# 3DEC8.net
KiCad netlist of a schematic drawn in EAGLE
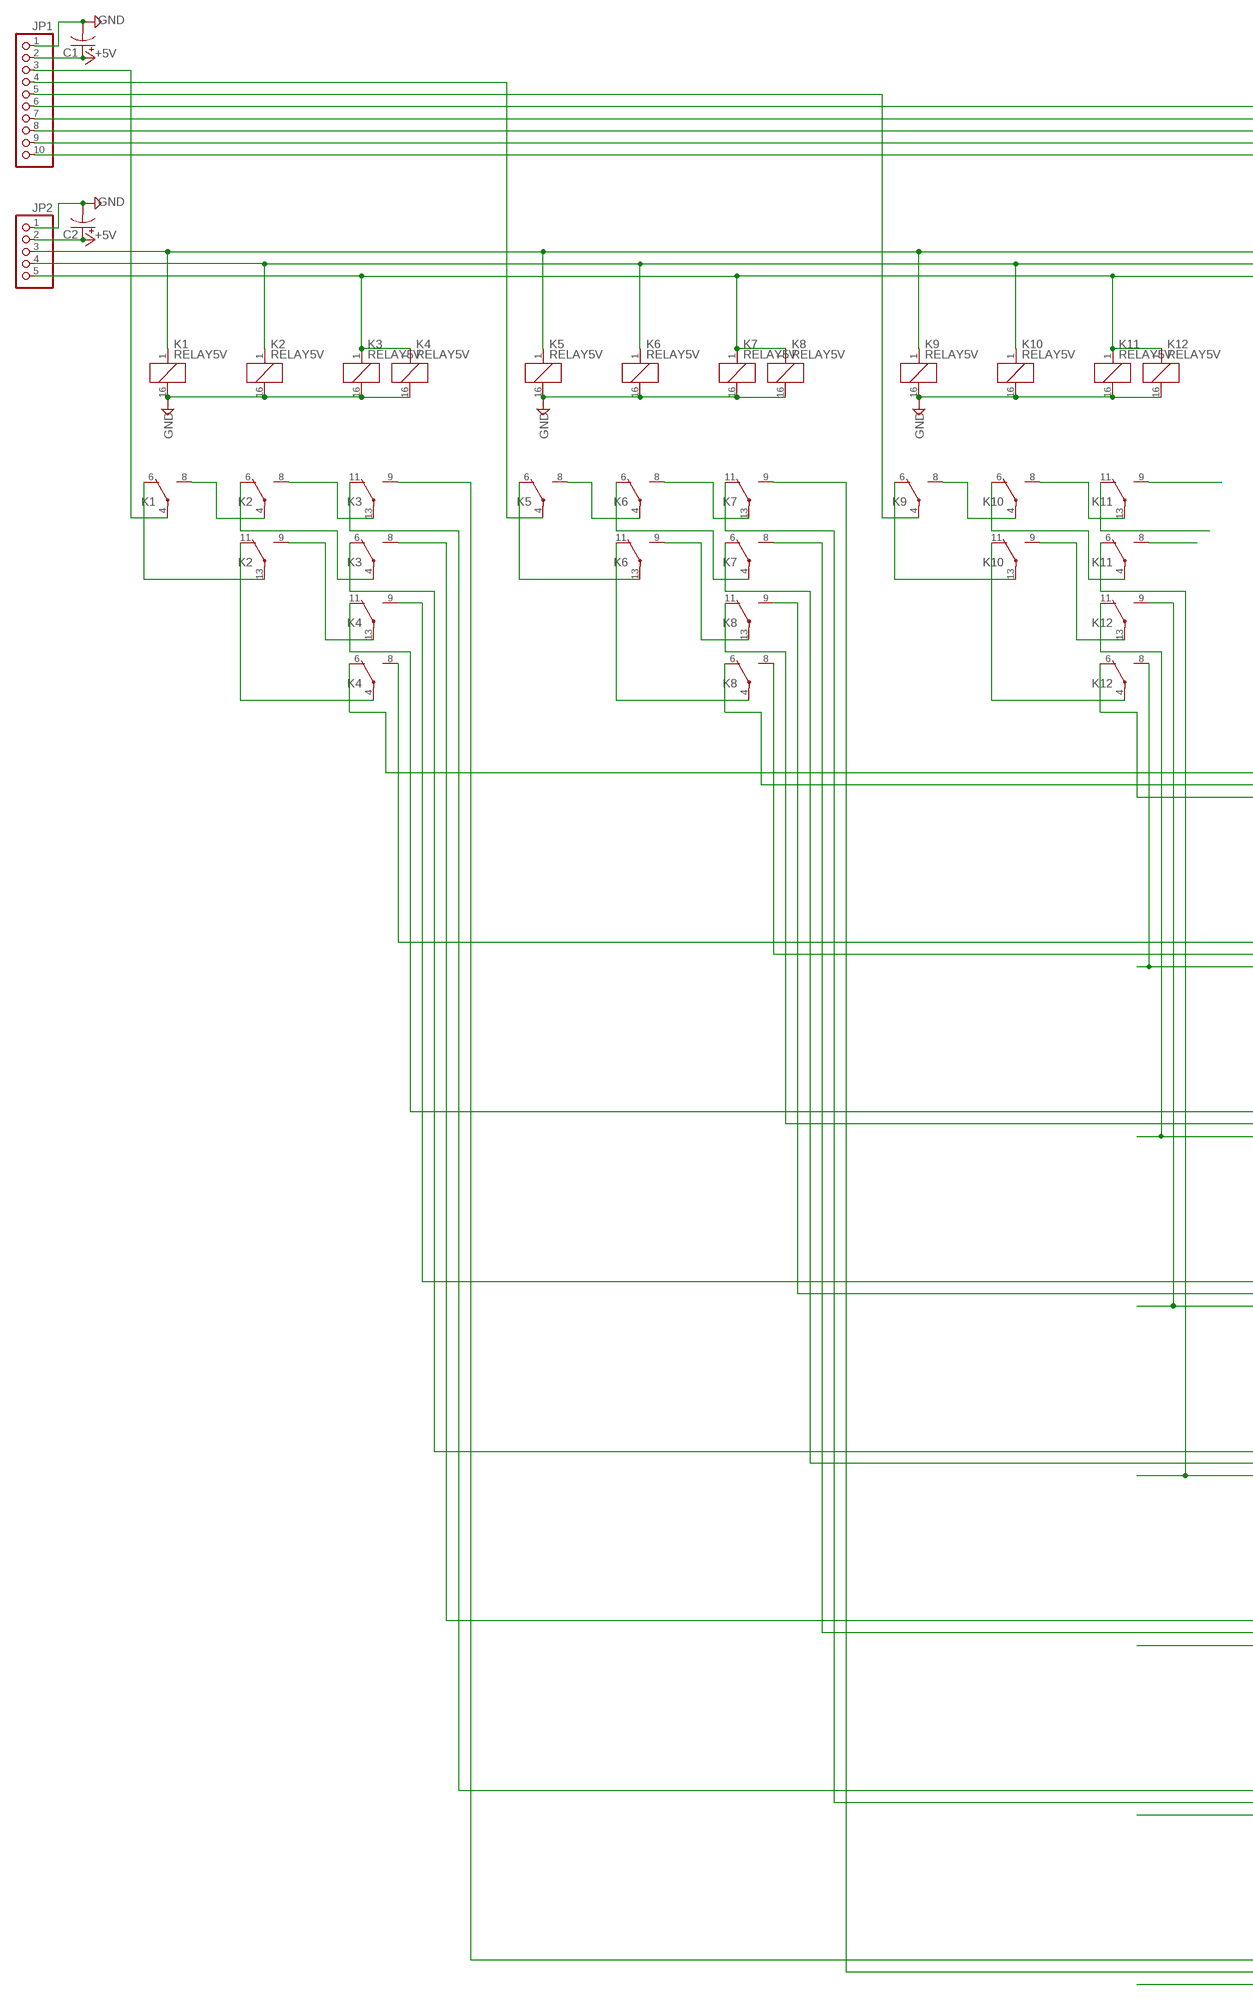
[diagram p0: schematic, sheet 1, part 1 of 2]
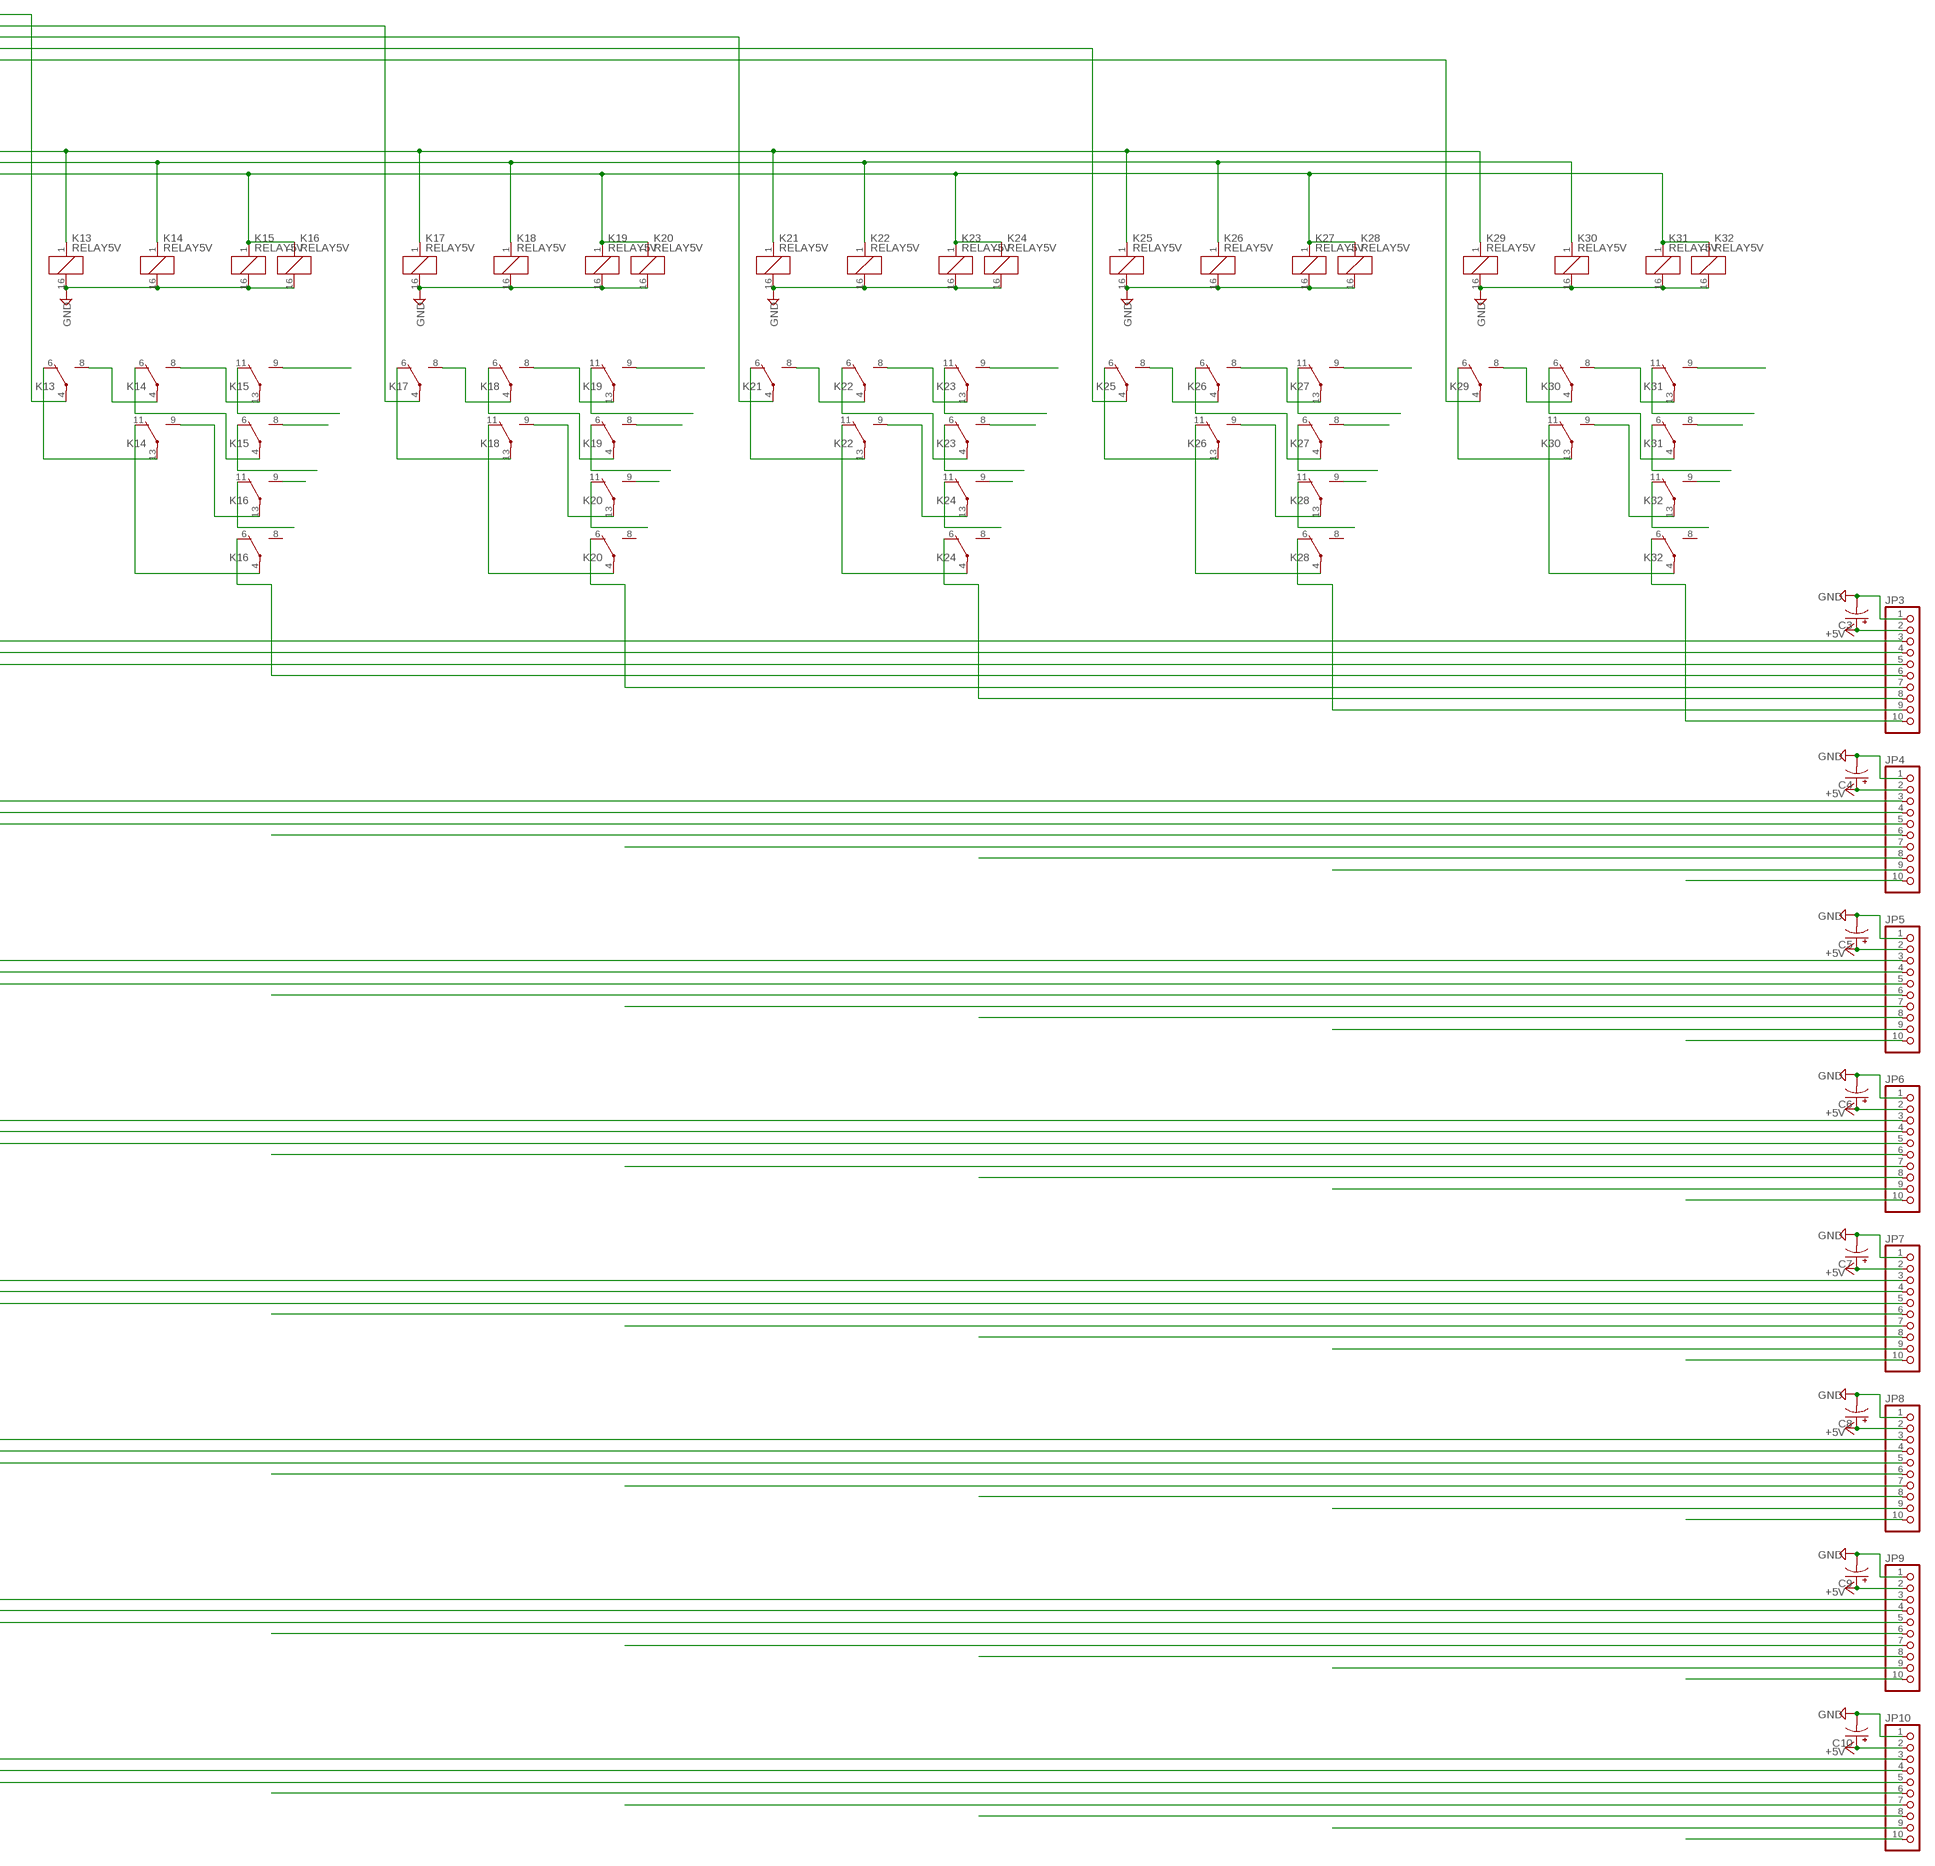
[diagram p1: schematic, sheet 1, part 2 of 2]

(export (version "E")
  (design (tool "Eeschema 10.0.6"))
  (components
    (comp (ref "C1")
      (value "CC-5-8.5")
      (footprint "eagle-import:E5-8,5")
      (libsource (lib "eagle-import") (part "CC-5-8.5"))
    )
    (comp (ref "C2")
      (value "CC-5-8.5")
      (footprint "eagle-import:E5-8,5")
      (libsource (lib "eagle-import") (part "CC-5-8.5"))
    )
    (comp (ref "C3")
      (value "CC-5-8.5")
      (footprint "eagle-import:E5-8,5")
      (libsource (lib "eagle-import") (part "CC-5-8.5"))
    )
    (comp (ref "C4")
      (value "CC-5-8.5")
      (footprint "eagle-import:E5-8,5")
      (libsource (lib "eagle-import") (part "CC-5-8.5"))
    )
    (comp (ref "C5")
      (value "CC-5-8.5")
      (footprint "eagle-import:E5-8,5")
      (libsource (lib "eagle-import") (part "CC-5-8.5"))
    )
    (comp (ref "C6")
      (value "CC-5-8.5")
      (footprint "eagle-import:E5-8,5")
      (libsource (lib "eagle-import") (part "CC-5-8.5"))
    )
    (comp (ref "C7")
      (value "CC-5-8.5")
      (footprint "eagle-import:E5-8,5")
      (libsource (lib "eagle-import") (part "CC-5-8.5"))
    )
    (comp (ref "C8")
      (value "CC-5-8.5")
      (footprint "eagle-import:E5-8,5")
      (libsource (lib "eagle-import") (part "CC-5-8.5"))
    )
    (comp (ref "C9")
      (value "CC-5-8.5")
      (footprint "eagle-import:E5-8,5")
      (libsource (lib "eagle-import") (part "CC-5-8.5"))
    )
    (comp (ref "C10")
      (value "CC-5-8.5")
      (footprint "eagle-import:E5-8,5")
      (libsource (lib "eagle-import") (part "CC-5-8.5"))
    )
    (comp (ref "JP1")
      (value "PINHD-1X10")
      (footprint "eagle-import:1X10")
      (libsource (lib "eagle-import") (part "PINHD-1X10"))
    )
    (comp (ref "JP2")
      (value "PINHD-1X5")
      (footprint "eagle-import:1X05")
      (libsource (lib "eagle-import") (part "PINHD-1X5"))
    )
    (comp (ref "JP3")
      (value "PINHD-1X10")
      (footprint "eagle-import:1X10")
      (libsource (lib "eagle-import") (part "PINHD-1X10"))
    )
    (comp (ref "JP4")
      (value "PINHD-1X10")
      (footprint "eagle-import:1X10")
      (libsource (lib "eagle-import") (part "PINHD-1X10"))
    )
    (comp (ref "JP5")
      (value "PINHD-1X10")
      (footprint "eagle-import:1X10")
      (libsource (lib "eagle-import") (part "PINHD-1X10"))
    )
    (comp (ref "JP6")
      (value "PINHD-1X10")
      (footprint "eagle-import:1X10")
      (libsource (lib "eagle-import") (part "PINHD-1X10"))
    )
    (comp (ref "JP7")
      (value "PINHD-1X10")
      (footprint "eagle-import:1X10")
      (libsource (lib "eagle-import") (part "PINHD-1X10"))
    )
    (comp (ref "JP8")
      (value "PINHD-1X10")
      (footprint "eagle-import:1X10")
      (libsource (lib "eagle-import") (part "PINHD-1X10"))
    )
    (comp (ref "JP9")
      (value "PINHD-1X10")
      (footprint "eagle-import:1X10")
      (libsource (lib "eagle-import") (part "PINHD-1X10"))
    )
    (comp (ref "JP10")
      (value "PINHD-1X10")
      (footprint "eagle-import:1X10")
      (libsource (lib "eagle-import") (part "PINHD-1X10"))
    )
    (comp (ref "K1")
      (value "RELAY5V")
      (footprint "eagle-import:DS-BT")
      (libsource (lib "eagle-import") (part "RELAY5V"))
    )
    (comp (ref "K2")
      (value "RELAY5V")
      (footprint "eagle-import:DS-BT")
      (libsource (lib "eagle-import") (part "RELAY5V"))
    )
    (comp (ref "K3")
      (value "RELAY5V")
      (footprint "eagle-import:DS-BT")
      (libsource (lib "eagle-import") (part "RELAY5V"))
    )
    (comp (ref "K4")
      (value "RELAY5V")
      (footprint "eagle-import:DS-BT")
      (libsource (lib "eagle-import") (part "RELAY5V"))
    )
    (comp (ref "K5")
      (value "RELAY5V")
      (footprint "eagle-import:DS-BT")
      (libsource (lib "eagle-import") (part "RELAY5V"))
    )
    (comp (ref "K6")
      (value "RELAY5V")
      (footprint "eagle-import:DS-BT")
      (libsource (lib "eagle-import") (part "RELAY5V"))
    )
    (comp (ref "K7")
      (value "RELAY5V")
      (footprint "eagle-import:DS-BT")
      (libsource (lib "eagle-import") (part "RELAY5V"))
    )
    (comp (ref "K8")
      (value "RELAY5V")
      (footprint "eagle-import:DS-BT")
      (libsource (lib "eagle-import") (part "RELAY5V"))
    )
    (comp (ref "K9")
      (value "RELAY5V")
      (footprint "eagle-import:DS-BT")
      (libsource (lib "eagle-import") (part "RELAY5V"))
    )
    (comp (ref "K10")
      (value "RELAY5V")
      (footprint "eagle-import:DS-BT")
      (libsource (lib "eagle-import") (part "RELAY5V"))
    )
    (comp (ref "K11")
      (value "RELAY5V")
      (footprint "eagle-import:DS-BT")
      (libsource (lib "eagle-import") (part "RELAY5V"))
    )
    (comp (ref "K12")
      (value "RELAY5V")
      (footprint "eagle-import:DS-BT")
      (libsource (lib "eagle-import") (part "RELAY5V"))
    )
    (comp (ref "K13")
      (value "RELAY5V")
      (footprint "eagle-import:DS-BT")
      (libsource (lib "eagle-import") (part "RELAY5V"))
    )
    (comp (ref "K14")
      (value "RELAY5V")
      (footprint "eagle-import:DS-BT")
      (libsource (lib "eagle-import") (part "RELAY5V"))
    )
    (comp (ref "K15")
      (value "RELAY5V")
      (footprint "eagle-import:DS-BT")
      (libsource (lib "eagle-import") (part "RELAY5V"))
    )
    (comp (ref "K16")
      (value "RELAY5V")
      (footprint "eagle-import:DS-BT")
      (libsource (lib "eagle-import") (part "RELAY5V"))
    )
    (comp (ref "K17")
      (value "RELAY5V")
      (footprint "eagle-import:DS-BT")
      (libsource (lib "eagle-import") (part "RELAY5V"))
    )
    (comp (ref "K18")
      (value "RELAY5V")
      (footprint "eagle-import:DS-BT")
      (libsource (lib "eagle-import") (part "RELAY5V"))
    )
    (comp (ref "K19")
      (value "RELAY5V")
      (footprint "eagle-import:DS-BT")
      (libsource (lib "eagle-import") (part "RELAY5V"))
    )
    (comp (ref "K20")
      (value "RELAY5V")
      (footprint "eagle-import:DS-BT")
      (libsource (lib "eagle-import") (part "RELAY5V"))
    )
    (comp (ref "K21")
      (value "RELAY5V")
      (footprint "eagle-import:DS-BT")
      (libsource (lib "eagle-import") (part "RELAY5V"))
    )
    (comp (ref "K22")
      (value "RELAY5V")
      (footprint "eagle-import:DS-BT")
      (libsource (lib "eagle-import") (part "RELAY5V"))
    )
    (comp (ref "K23")
      (value "RELAY5V")
      (footprint "eagle-import:DS-BT")
      (libsource (lib "eagle-import") (part "RELAY5V"))
    )
    (comp (ref "K24")
      (value "RELAY5V")
      (footprint "eagle-import:DS-BT")
      (libsource (lib "eagle-import") (part "RELAY5V"))
    )
    (comp (ref "K25")
      (value "RELAY5V")
      (footprint "eagle-import:DS-BT")
      (libsource (lib "eagle-import") (part "RELAY5V"))
    )
    (comp (ref "K26")
      (value "RELAY5V")
      (footprint "eagle-import:DS-BT")
      (libsource (lib "eagle-import") (part "RELAY5V"))
    )
    (comp (ref "K27")
      (value "RELAY5V")
      (footprint "eagle-import:DS-BT")
      (libsource (lib "eagle-import") (part "RELAY5V"))
    )
    (comp (ref "K28")
      (value "RELAY5V")
      (footprint "eagle-import:DS-BT")
      (libsource (lib "eagle-import") (part "RELAY5V"))
    )
    (comp (ref "K29")
      (value "RELAY5V")
      (footprint "eagle-import:DS-BT")
      (libsource (lib "eagle-import") (part "RELAY5V"))
    )
    (comp (ref "K30")
      (value "RELAY5V")
      (footprint "eagle-import:DS-BT")
      (libsource (lib "eagle-import") (part "RELAY5V"))
    )
    (comp (ref "K31")
      (value "RELAY5V")
      (footprint "eagle-import:DS-BT")
      (libsource (lib "eagle-import") (part "RELAY5V"))
    )
    (comp (ref "K32")
      (value "RELAY5V")
      (footprint "eagle-import:DS-BT")
      (libsource (lib "eagle-import") (part "RELAY5V"))
    )
  )
  (nets
    (net (code "1") (name "+5V") (class "Default")
      (node (ref "C1") (pin "+") (pinfunction "+_+") (pintype "passive"))
      (node (ref "C10") (pin "+") (pinfunction "+_+") (pintype "passive"))
      (node (ref "C2") (pin "+") (pinfunction "+_+") (pintype "passive"))
      (node (ref "C3") (pin "+") (pinfunction "+_+") (pintype "passive"))
      (node (ref "C4") (pin "+") (pinfunction "+_+") (pintype "passive"))
      (node (ref "C5") (pin "+") (pinfunction "+_+") (pintype "passive"))
      (node (ref "C6") (pin "+") (pinfunction "+_+") (pintype "passive"))
      (node (ref "C7") (pin "+") (pinfunction "+_+") (pintype "passive"))
      (node (ref "C8") (pin "+") (pinfunction "+_+") (pintype "passive"))
      (node (ref "C9") (pin "+") (pinfunction "+_+") (pintype "passive"))
      (node (ref "JP1") (pin "2") (pinfunction "2_2") (pintype "passive"))
      (node (ref "JP10") (pin "2") (pinfunction "2_2") (pintype "passive"))
      (node (ref "JP2") (pin "2") (pinfunction "2_2") (pintype "passive"))
      (node (ref "JP3") (pin "2") (pinfunction "2_2") (pintype "passive"))
      (node (ref "JP4") (pin "2") (pinfunction "2_2") (pintype "passive"))
      (node (ref "JP5") (pin "2") (pinfunction "2_2") (pintype "passive"))
      (node (ref "JP6") (pin "2") (pinfunction "2_2") (pintype "passive"))
      (node (ref "JP7") (pin "2") (pinfunction "2_2") (pintype "passive"))
      (node (ref "JP8") (pin "2") (pinfunction "2_2") (pintype "passive"))
      (node (ref "JP9") (pin "2") (pinfunction "2_2") (pintype "passive"))
    )
    (net (code "2") (name "GND") (class "Default")
      (node (ref "C1") (pin "-") (pinfunction "-_-") (pintype "passive"))
      (node (ref "C10") (pin "-") (pinfunction "-_-") (pintype "passive"))
      (node (ref "C2") (pin "-") (pinfunction "-_-") (pintype "passive"))
      (node (ref "C3") (pin "-") (pinfunction "-_-") (pintype "passive"))
      (node (ref "C4") (pin "-") (pinfunction "-_-") (pintype "passive"))
      (node (ref "C5") (pin "-") (pinfunction "-_-") (pintype "passive"))
      (node (ref "C6") (pin "-") (pinfunction "-_-") (pintype "passive"))
      (node (ref "C7") (pin "-") (pinfunction "-_-") (pintype "passive"))
      (node (ref "C8") (pin "-") (pinfunction "-_-") (pintype "passive"))
      (node (ref "C9") (pin "-") (pinfunction "-_-") (pintype "passive"))
      (node (ref "JP1") (pin "1") (pinfunction "1_1") (pintype "passive"))
      (node (ref "JP10") (pin "1") (pinfunction "1_1") (pintype "passive"))
      (node (ref "JP2") (pin "1") (pinfunction "1_1") (pintype "passive"))
      (node (ref "JP3") (pin "1") (pinfunction "1_1") (pintype "passive"))
      (node (ref "JP4") (pin "1") (pinfunction "1_1") (pintype "passive"))
      (node (ref "JP5") (pin "1") (pinfunction "1_1") (pintype "passive"))
      (node (ref "JP6") (pin "1") (pinfunction "1_1") (pintype "passive"))
      (node (ref "JP7") (pin "1") (pinfunction "1_1") (pintype "passive"))
      (node (ref "JP8") (pin "1") (pinfunction "1_1") (pintype "passive"))
      (node (ref "JP9") (pin "1") (pinfunction "1_1") (pintype "passive"))
      (node (ref "K1") (pin "16") (pinfunction "-_16") (pintype "passive"))
      (node (ref "K10") (pin "16") (pinfunction "-_16") (pintype "passive"))
      (node (ref "K11") (pin "16") (pinfunction "-_16") (pintype "passive"))
      (node (ref "K12") (pin "16") (pinfunction "-_16") (pintype "passive"))
      (node (ref "K13") (pin "16") (pinfunction "-_16") (pintype "passive"))
      (node (ref "K14") (pin "16") (pinfunction "-_16") (pintype "passive"))
      (node (ref "K15") (pin "16") (pinfunction "-_16") (pintype "passive"))
      (node (ref "K16") (pin "16") (pinfunction "-_16") (pintype "passive"))
      (node (ref "K17") (pin "16") (pinfunction "-_16") (pintype "passive"))
      (node (ref "K18") (pin "16") (pinfunction "-_16") (pintype "passive"))
      (node (ref "K19") (pin "16") (pinfunction "-_16") (pintype "passive"))
      (node (ref "K2") (pin "16") (pinfunction "-_16") (pintype "passive"))
      (node (ref "K20") (pin "16") (pinfunction "-_16") (pintype "passive"))
      (node (ref "K21") (pin "16") (pinfunction "-_16") (pintype "passive"))
      (node (ref "K22") (pin "16") (pinfunction "-_16") (pintype "passive"))
      (node (ref "K23") (pin "16") (pinfunction "-_16") (pintype "passive"))
      (node (ref "K24") (pin "16") (pinfunction "-_16") (pintype "passive"))
      (node (ref "K25") (pin "16") (pinfunction "-_16") (pintype "passive"))
      (node (ref "K26") (pin "16") (pinfunction "-_16") (pintype "passive"))
      (node (ref "K27") (pin "16") (pinfunction "-_16") (pintype "passive"))
      (node (ref "K28") (pin "16") (pinfunction "-_16") (pintype "passive"))
      (node (ref "K29") (pin "16") (pinfunction "-_16") (pintype "passive"))
      (node (ref "K3") (pin "16") (pinfunction "-_16") (pintype "passive"))
      (node (ref "K30") (pin "16") (pinfunction "-_16") (pintype "passive"))
      (node (ref "K31") (pin "16") (pinfunction "-_16") (pintype "passive"))
      (node (ref "K32") (pin "16") (pinfunction "-_16") (pintype "passive"))
      (node (ref "K4") (pin "16") (pinfunction "-_16") (pintype "passive"))
      (node (ref "K5") (pin "16") (pinfunction "-_16") (pintype "passive"))
      (node (ref "K6") (pin "16") (pinfunction "-_16") (pintype "passive"))
      (node (ref "K7") (pin "16") (pinfunction "-_16") (pintype "passive"))
      (node (ref "K8") (pin "16") (pinfunction "-_16") (pintype "passive"))
      (node (ref "K9") (pin "16") (pinfunction "-_16") (pintype "passive"))
    )
    (net (code "3") (name "Net-(K1B-O)") (class "Default")
      (node (ref "K1") (pin "6") (pinfunction "O_6") (pintype "passive"))
      (node (ref "K2") (pin "13") (pinfunction "P_13") (pintype "passive"))
    )
    (net (code "4") (name "Net-(K1B-P)") (class "Default")
      (node (ref "JP1") (pin "3") (pinfunction "3_3") (pintype "passive"))
      (node (ref "K1") (pin "4") (pinfunction "P_4") (pintype "passive"))
    )
    (net (code "5") (name "Net-(K1B-S)") (class "Default")
      (node (ref "K1") (pin "8") (pinfunction "S_8") (pintype "passive"))
      (node (ref "K2") (pin "4") (pinfunction "P_4") (pintype "passive"))
    )
    (net (code "6") (name "Net-(K2B-O)") (class "Default")
      (node (ref "K2") (pin "6") (pinfunction "O_6") (pintype "passive"))
      (node (ref "K3") (pin "4") (pinfunction "P_4") (pintype "passive"))
    )
    (net (code "7") (name "Net-(K2B-S)") (class "Default")
      (node (ref "K2") (pin "8") (pinfunction "S_8") (pintype "passive"))
      (node (ref "K3") (pin "13") (pinfunction "P_13") (pintype "passive"))
    )
    (net (code "8") (name "Net-(K2C-O)") (class "Default")
      (node (ref "K2") (pin "11") (pinfunction "O_11") (pintype "passive"))
      (node (ref "K4") (pin "4") (pinfunction "P_4") (pintype "passive"))
    )
    (net (code "9") (name "Net-(K2C-S)") (class "Default")
      (node (ref "K2") (pin "9") (pinfunction "S_9") (pintype "passive"))
      (node (ref "K4") (pin "13") (pinfunction "P_13") (pintype "passive"))
    )
    (net (code "10") (name "Net-(K3B-O)") (class "Default")
      (node (ref "JP7") (pin "3") (pinfunction "3_3") (pintype "passive"))
      (node (ref "K3") (pin "6") (pinfunction "O_6") (pintype "passive"))
    )
    (net (code "11") (name "Net-(K3B-S)") (class "Default")
      (node (ref "JP8") (pin "3") (pinfunction "3_3") (pintype "passive"))
      (node (ref "K3") (pin "8") (pinfunction "S_8") (pintype "passive"))
    )
    (net (code "12") (name "Net-(K3C-O)") (class "Default")
      (node (ref "JP9") (pin "3") (pinfunction "3_3") (pintype "passive"))
      (node (ref "K3") (pin "11") (pinfunction "O_11") (pintype "passive"))
    )
    (net (code "13") (name "Net-(K3C-S)") (class "Default")
      (node (ref "JP10") (pin "3") (pinfunction "3_3") (pintype "passive"))
      (node (ref "K3") (pin "9") (pinfunction "S_9") (pintype "passive"))
    )
    (net (code "14") (name "Net-(K4B-O)") (class "Default")
      (node (ref "JP3") (pin "3") (pinfunction "3_3") (pintype "passive"))
      (node (ref "K4") (pin "6") (pinfunction "O_6") (pintype "passive"))
    )
    (net (code "15") (name "Net-(K4B-S)") (class "Default")
      (node (ref "JP4") (pin "3") (pinfunction "3_3") (pintype "passive"))
      (node (ref "K4") (pin "8") (pinfunction "S_8") (pintype "passive"))
    )
    (net (code "16") (name "Net-(K4C-O)") (class "Default")
      (node (ref "JP5") (pin "3") (pinfunction "3_3") (pintype "passive"))
      (node (ref "K4") (pin "11") (pinfunction "O_11") (pintype "passive"))
    )
    (net (code "17") (name "Net-(K4C-S)") (class "Default")
      (node (ref "JP6") (pin "3") (pinfunction "3_3") (pintype "passive"))
      (node (ref "K4") (pin "9") (pinfunction "S_9") (pintype "passive"))
    )
    (net (code "18") (name "Net-(K5B-O)") (class "Default")
      (node (ref "K5") (pin "6") (pinfunction "O_6") (pintype "passive"))
      (node (ref "K6") (pin "13") (pinfunction "P_13") (pintype "passive"))
    )
    (net (code "19") (name "Net-(K5B-P)") (class "Default")
      (node (ref "JP1") (pin "4") (pinfunction "4_4") (pintype "passive"))
      (node (ref "K5") (pin "4") (pinfunction "P_4") (pintype "passive"))
    )
    (net (code "20") (name "Net-(K5B-S)") (class "Default")
      (node (ref "K5") (pin "8") (pinfunction "S_8") (pintype "passive"))
      (node (ref "K6") (pin "4") (pinfunction "P_4") (pintype "passive"))
    )
    (net (code "21") (name "Net-(K6B-O)") (class "Default")
      (node (ref "K6") (pin "6") (pinfunction "O_6") (pintype "passive"))
      (node (ref "K7") (pin "4") (pinfunction "P_4") (pintype "passive"))
    )
    (net (code "22") (name "Net-(K6B-S)") (class "Default")
      (node (ref "K6") (pin "8") (pinfunction "S_8") (pintype "passive"))
      (node (ref "K7") (pin "13") (pinfunction "P_13") (pintype "passive"))
    )
    (net (code "23") (name "Net-(K6C-O)") (class "Default")
      (node (ref "K6") (pin "11") (pinfunction "O_11") (pintype "passive"))
      (node (ref "K8") (pin "4") (pinfunction "P_4") (pintype "passive"))
    )
    (net (code "24") (name "Net-(K6C-S)") (class "Default")
      (node (ref "K6") (pin "9") (pinfunction "S_9") (pintype "passive"))
      (node (ref "K8") (pin "13") (pinfunction "P_13") (pintype "passive"))
    )
    (net (code "25") (name "Net-(K7B-O)") (class "Default")
      (node (ref "JP7") (pin "4") (pinfunction "4_4") (pintype "passive"))
      (node (ref "K7") (pin "6") (pinfunction "O_6") (pintype "passive"))
    )
    (net (code "26") (name "Net-(K7B-S)") (class "Default")
      (node (ref "JP8") (pin "4") (pinfunction "4_4") (pintype "passive"))
      (node (ref "K7") (pin "8") (pinfunction "S_8") (pintype "passive"))
    )
    (net (code "27") (name "Net-(K7C-O)") (class "Default")
      (node (ref "JP9") (pin "4") (pinfunction "4_4") (pintype "passive"))
      (node (ref "K7") (pin "11") (pinfunction "O_11") (pintype "passive"))
    )
    (net (code "28") (name "Net-(K7C-S)") (class "Default")
      (node (ref "JP10") (pin "4") (pinfunction "4_4") (pintype "passive"))
      (node (ref "K7") (pin "9") (pinfunction "S_9") (pintype "passive"))
    )
    (net (code "29") (name "Net-(K8B-O)") (class "Default")
      (node (ref "JP3") (pin "4") (pinfunction "4_4") (pintype "passive"))
      (node (ref "K8") (pin "6") (pinfunction "O_6") (pintype "passive"))
    )
    (net (code "30") (name "Net-(K8B-S)") (class "Default")
      (node (ref "JP4") (pin "4") (pinfunction "4_4") (pintype "passive"))
      (node (ref "K8") (pin "8") (pinfunction "S_8") (pintype "passive"))
    )
    (net (code "31") (name "Net-(K8C-O)") (class "Default")
      (node (ref "JP5") (pin "4") (pinfunction "4_4") (pintype "passive"))
      (node (ref "K8") (pin "11") (pinfunction "O_11") (pintype "passive"))
    )
    (net (code "32") (name "Net-(K8C-S)") (class "Default")
      (node (ref "JP6") (pin "4") (pinfunction "4_4") (pintype "passive"))
      (node (ref "K8") (pin "9") (pinfunction "S_9") (pintype "passive"))
    )
    (net (code "33") (name "Net-(K9B-P)") (class "Default")
      (node (ref "JP1") (pin "5") (pinfunction "5_5") (pintype "passive"))
      (node (ref "K9") (pin "4") (pinfunction "P_4") (pintype "passive"))
    )
    (net (code "34") (name "Net-(K10A-+)") (class "Default")
      (node (ref "JP2") (pin "4") (pinfunction "4_4") (pintype "passive"))
      (node (ref "K10") (pin "1") (pinfunction "+_1") (pintype "passive"))
      (node (ref "K14") (pin "1") (pinfunction "+_1") (pintype "passive"))
      (node (ref "K18") (pin "1") (pinfunction "+_1") (pintype "passive"))
      (node (ref "K2") (pin "1") (pinfunction "+_1") (pintype "passive"))
      (node (ref "K22") (pin "1") (pinfunction "+_1") (pintype "passive"))
      (node (ref "K26") (pin "1") (pinfunction "+_1") (pintype "passive"))
      (node (ref "K30") (pin "1") (pinfunction "+_1") (pintype "passive"))
      (node (ref "K6") (pin "1") (pinfunction "+_1") (pintype "passive"))
    )
    (net (code "35") (name "Net-(K10B-O)") (class "Default")
      (node (ref "K10") (pin "6") (pinfunction "O_6") (pintype "passive"))
      (node (ref "K11") (pin "4") (pinfunction "P_4") (pintype "passive"))
    )
    (net (code "36") (name "Net-(K10B-P)") (class "Default")
      (node (ref "K10") (pin "4") (pinfunction "P_4") (pintype "passive"))
      (node (ref "K9") (pin "8") (pinfunction "S_8") (pintype "passive"))
    )
    (net (code "37") (name "Net-(K10B-S)") (class "Default")
      (node (ref "K10") (pin "8") (pinfunction "S_8") (pintype "passive"))
      (node (ref "K11") (pin "13") (pinfunction "P_13") (pintype "passive"))
    )
    (net (code "38") (name "Net-(K10C-O)") (class "Default")
      (node (ref "K10") (pin "11") (pinfunction "O_11") (pintype "passive"))
      (node (ref "K12") (pin "4") (pinfunction "P_4") (pintype "passive"))
    )
    (net (code "39") (name "Net-(K10C-P)") (class "Default")
      (node (ref "K10") (pin "13") (pinfunction "P_13") (pintype "passive"))
      (node (ref "K9") (pin "6") (pinfunction "O_6") (pintype "passive"))
    )
    (net (code "40") (name "Net-(K10C-S)") (class "Default")
      (node (ref "K10") (pin "9") (pinfunction "S_9") (pintype "passive"))
      (node (ref "K12") (pin "13") (pinfunction "P_13") (pintype "passive"))
    )
    (net (code "41") (name "Net-(K11A-+)") (class "Default")
      (node (ref "JP2") (pin "5") (pinfunction "5_5") (pintype "passive"))
      (node (ref "K11") (pin "1") (pinfunction "+_1") (pintype "passive"))
      (node (ref "K12") (pin "1") (pinfunction "+_1") (pintype "passive"))
      (node (ref "K15") (pin "1") (pinfunction "+_1") (pintype "passive"))
      (node (ref "K16") (pin "1") (pinfunction "+_1") (pintype "passive"))
      (node (ref "K19") (pin "1") (pinfunction "+_1") (pintype "passive"))
      (node (ref "K20") (pin "1") (pinfunction "+_1") (pintype "passive"))
      (node (ref "K23") (pin "1") (pinfunction "+_1") (pintype "passive"))
      (node (ref "K24") (pin "1") (pinfunction "+_1") (pintype "passive"))
      (node (ref "K27") (pin "1") (pinfunction "+_1") (pintype "passive"))
      (node (ref "K28") (pin "1") (pinfunction "+_1") (pintype "passive"))
      (node (ref "K3") (pin "1") (pinfunction "+_1") (pintype "passive"))
      (node (ref "K31") (pin "1") (pinfunction "+_1") (pintype "passive"))
      (node (ref "K32") (pin "1") (pinfunction "+_1") (pintype "passive"))
      (node (ref "K4") (pin "1") (pinfunction "+_1") (pintype "passive"))
      (node (ref "K7") (pin "1") (pinfunction "+_1") (pintype "passive"))
      (node (ref "K8") (pin "1") (pinfunction "+_1") (pintype "passive"))
    )
    (net (code "42") (name "Net-(K11B-O)") (class "Default")
      (node (ref "JP7") (pin "5") (pinfunction "5_5") (pintype "passive"))
      (node (ref "K11") (pin "6") (pinfunction "O_6") (pintype "passive"))
    )
    (net (code "43") (name "Net-(K12B-O)") (class "Default")
      (node (ref "JP3") (pin "5") (pinfunction "5_5") (pintype "passive"))
      (node (ref "K12") (pin "6") (pinfunction "O_6") (pintype "passive"))
    )
    (net (code "44") (name "Net-(K12B-S)") (class "Default")
      (node (ref "JP4") (pin "5") (pinfunction "5_5") (pintype "passive"))
      (node (ref "K12") (pin "8") (pinfunction "S_8") (pintype "passive"))
    )
    (net (code "45") (name "Net-(K12C-O)") (class "Default")
      (node (ref "JP5") (pin "5") (pinfunction "5_5") (pintype "passive"))
      (node (ref "K12") (pin "11") (pinfunction "O_11") (pintype "passive"))
    )
    (net (code "46") (name "Net-(K12C-S)") (class "Default")
      (node (ref "JP6") (pin "5") (pinfunction "5_5") (pintype "passive"))
      (node (ref "K12") (pin "9") (pinfunction "S_9") (pintype "passive"))
    )
    (net (code "47") (name "Net-(K13A-+)") (class "Default")
      (node (ref "JP2") (pin "3") (pinfunction "3_3") (pintype "passive"))
      (node (ref "K1") (pin "1") (pinfunction "+_1") (pintype "passive"))
      (node (ref "K13") (pin "1") (pinfunction "+_1") (pintype "passive"))
      (node (ref "K17") (pin "1") (pinfunction "+_1") (pintype "passive"))
      (node (ref "K21") (pin "1") (pinfunction "+_1") (pintype "passive"))
      (node (ref "K25") (pin "1") (pinfunction "+_1") (pintype "passive"))
      (node (ref "K29") (pin "1") (pinfunction "+_1") (pintype "passive"))
      (node (ref "K5") (pin "1") (pinfunction "+_1") (pintype "passive"))
      (node (ref "K9") (pin "1") (pinfunction "+_1") (pintype "passive"))
    )
    (net (code "48") (name "Net-(K13B-O)") (class "Default")
      (node (ref "K13") (pin "6") (pinfunction "O_6") (pintype "passive"))
      (node (ref "K14") (pin "13") (pinfunction "P_13") (pintype "passive"))
    )
    (net (code "49") (name "Net-(K13B-P)") (class "Default")
      (node (ref "JP1") (pin "6") (pinfunction "6_6") (pintype "passive"))
      (node (ref "K13") (pin "4") (pinfunction "P_4") (pintype "passive"))
    )
    (net (code "50") (name "Net-(K13B-S)") (class "Default")
      (node (ref "K13") (pin "8") (pinfunction "S_8") (pintype "passive"))
      (node (ref "K14") (pin "4") (pinfunction "P_4") (pintype "passive"))
    )
    (net (code "51") (name "Net-(K14B-O)") (class "Default")
      (node (ref "K14") (pin "6") (pinfunction "O_6") (pintype "passive"))
      (node (ref "K15") (pin "4") (pinfunction "P_4") (pintype "passive"))
    )
    (net (code "52") (name "Net-(K14B-S)") (class "Default")
      (node (ref "K14") (pin "8") (pinfunction "S_8") (pintype "passive"))
      (node (ref "K15") (pin "13") (pinfunction "P_13") (pintype "passive"))
    )
    (net (code "53") (name "Net-(K14C-O)") (class "Default")
      (node (ref "K14") (pin "11") (pinfunction "O_11") (pintype "passive"))
      (node (ref "K16") (pin "4") (pinfunction "P_4") (pintype "passive"))
    )
    (net (code "54") (name "Net-(K14C-S)") (class "Default")
      (node (ref "K14") (pin "9") (pinfunction "S_9") (pintype "passive"))
      (node (ref "K16") (pin "13") (pinfunction "P_13") (pintype "passive"))
    )
    (net (code "55") (name "Net-(K16B-O)") (class "Default")
      (node (ref "JP3") (pin "6") (pinfunction "6_6") (pintype "passive"))
      (node (ref "K16") (pin "6") (pinfunction "O_6") (pintype "passive"))
    )
    (net (code "56") (name "Net-(K17B-O)") (class "Default")
      (node (ref "K17") (pin "6") (pinfunction "O_6") (pintype "passive"))
      (node (ref "K18") (pin "13") (pinfunction "P_13") (pintype "passive"))
    )
    (net (code "57") (name "Net-(K17B-P)") (class "Default")
      (node (ref "JP1") (pin "7") (pinfunction "7_7") (pintype "passive"))
      (node (ref "K17") (pin "4") (pinfunction "P_4") (pintype "passive"))
    )
    (net (code "58") (name "Net-(K17B-S)") (class "Default")
      (node (ref "K17") (pin "8") (pinfunction "S_8") (pintype "passive"))
      (node (ref "K18") (pin "4") (pinfunction "P_4") (pintype "passive"))
    )
    (net (code "59") (name "Net-(K18B-O)") (class "Default")
      (node (ref "K18") (pin "6") (pinfunction "O_6") (pintype "passive"))
      (node (ref "K19") (pin "4") (pinfunction "P_4") (pintype "passive"))
    )
    (net (code "60") (name "Net-(K18B-S)") (class "Default")
      (node (ref "K18") (pin "8") (pinfunction "S_8") (pintype "passive"))
      (node (ref "K19") (pin "13") (pinfunction "P_13") (pintype "passive"))
    )
    (net (code "61") (name "Net-(K18C-O)") (class "Default")
      (node (ref "K18") (pin "11") (pinfunction "O_11") (pintype "passive"))
      (node (ref "K20") (pin "4") (pinfunction "P_4") (pintype "passive"))
    )
    (net (code "62") (name "Net-(K18C-S)") (class "Default")
      (node (ref "K18") (pin "9") (pinfunction "S_9") (pintype "passive"))
      (node (ref "K20") (pin "13") (pinfunction "P_13") (pintype "passive"))
    )
    (net (code "63") (name "Net-(K20B-O)") (class "Default")
      (node (ref "JP3") (pin "7") (pinfunction "7_7") (pintype "passive"))
      (node (ref "K20") (pin "6") (pinfunction "O_6") (pintype "passive"))
    )
    (net (code "64") (name "Net-(K21B-O)") (class "Default")
      (node (ref "K21") (pin "6") (pinfunction "O_6") (pintype "passive"))
      (node (ref "K22") (pin "13") (pinfunction "P_13") (pintype "passive"))
    )
    (net (code "65") (name "Net-(K21B-P)") (class "Default")
      (node (ref "JP1") (pin "8") (pinfunction "8_8") (pintype "passive"))
      (node (ref "K21") (pin "4") (pinfunction "P_4") (pintype "passive"))
    )
    (net (code "66") (name "Net-(K21B-S)") (class "Default")
      (node (ref "K21") (pin "8") (pinfunction "S_8") (pintype "passive"))
      (node (ref "K22") (pin "4") (pinfunction "P_4") (pintype "passive"))
    )
    (net (code "67") (name "Net-(K22B-O)") (class "Default")
      (node (ref "K22") (pin "6") (pinfunction "O_6") (pintype "passive"))
      (node (ref "K23") (pin "4") (pinfunction "P_4") (pintype "passive"))
    )
    (net (code "68") (name "Net-(K22B-S)") (class "Default")
      (node (ref "K22") (pin "8") (pinfunction "S_8") (pintype "passive"))
      (node (ref "K23") (pin "13") (pinfunction "P_13") (pintype "passive"))
    )
    (net (code "69") (name "Net-(K22C-O)") (class "Default")
      (node (ref "K22") (pin "11") (pinfunction "O_11") (pintype "passive"))
      (node (ref "K24") (pin "4") (pinfunction "P_4") (pintype "passive"))
    )
    (net (code "70") (name "Net-(K22C-S)") (class "Default")
      (node (ref "K22") (pin "9") (pinfunction "S_9") (pintype "passive"))
      (node (ref "K24") (pin "13") (pinfunction "P_13") (pintype "passive"))
    )
    (net (code "71") (name "Net-(K24B-O)") (class "Default")
      (node (ref "JP3") (pin "8") (pinfunction "8_8") (pintype "passive"))
      (node (ref "K24") (pin "6") (pinfunction "O_6") (pintype "passive"))
    )
    (net (code "72") (name "Net-(K25B-O)") (class "Default")
      (node (ref "K25") (pin "6") (pinfunction "O_6") (pintype "passive"))
      (node (ref "K26") (pin "13") (pinfunction "P_13") (pintype "passive"))
    )
    (net (code "73") (name "Net-(K25B-P)") (class "Default")
      (node (ref "JP1") (pin "9") (pinfunction "9_9") (pintype "passive"))
      (node (ref "K25") (pin "4") (pinfunction "P_4") (pintype "passive"))
    )
    (net (code "74") (name "Net-(K25B-S)") (class "Default")
      (node (ref "K25") (pin "8") (pinfunction "S_8") (pintype "passive"))
      (node (ref "K26") (pin "4") (pinfunction "P_4") (pintype "passive"))
    )
    (net (code "75") (name "Net-(K26B-O)") (class "Default")
      (node (ref "K26") (pin "6") (pinfunction "O_6") (pintype "passive"))
      (node (ref "K27") (pin "4") (pinfunction "P_4") (pintype "passive"))
    )
    (net (code "76") (name "Net-(K26B-S)") (class "Default")
      (node (ref "K26") (pin "8") (pinfunction "S_8") (pintype "passive"))
      (node (ref "K27") (pin "13") (pinfunction "P_13") (pintype "passive"))
    )
    (net (code "77") (name "Net-(K26C-O)") (class "Default")
      (node (ref "K26") (pin "11") (pinfunction "O_11") (pintype "passive"))
      (node (ref "K28") (pin "4") (pinfunction "P_4") (pintype "passive"))
    )
    (net (code "78") (name "Net-(K26C-S)") (class "Default")
      (node (ref "K26") (pin "9") (pinfunction "S_9") (pintype "passive"))
      (node (ref "K28") (pin "13") (pinfunction "P_13") (pintype "passive"))
    )
    (net (code "79") (name "Net-(K28B-O)") (class "Default")
      (node (ref "JP3") (pin "9") (pinfunction "9_9") (pintype "passive"))
      (node (ref "K28") (pin "6") (pinfunction "O_6") (pintype "passive"))
    )
    (net (code "80") (name "Net-(K29B-O)") (class "Default")
      (node (ref "K29") (pin "6") (pinfunction "O_6") (pintype "passive"))
      (node (ref "K30") (pin "13") (pinfunction "P_13") (pintype "passive"))
    )
    (net (code "81") (name "Net-(K29B-P)") (class "Default")
      (node (ref "JP1") (pin "10") (pinfunction "10_10") (pintype "passive"))
      (node (ref "K29") (pin "4") (pinfunction "P_4") (pintype "passive"))
    )
    (net (code "82") (name "Net-(K29B-S)") (class "Default")
      (node (ref "K29") (pin "8") (pinfunction "S_8") (pintype "passive"))
      (node (ref "K30") (pin "4") (pinfunction "P_4") (pintype "passive"))
    )
    (net (code "83") (name "Net-(K30B-O)") (class "Default")
      (node (ref "K30") (pin "6") (pinfunction "O_6") (pintype "passive"))
      (node (ref "K31") (pin "4") (pinfunction "P_4") (pintype "passive"))
    )
    (net (code "84") (name "Net-(K30B-S)") (class "Default")
      (node (ref "K30") (pin "8") (pinfunction "S_8") (pintype "passive"))
      (node (ref "K31") (pin "13") (pinfunction "P_13") (pintype "passive"))
    )
    (net (code "85") (name "Net-(K30C-O)") (class "Default")
      (node (ref "K30") (pin "11") (pinfunction "O_11") (pintype "passive"))
      (node (ref "K32") (pin "4") (pinfunction "P_4") (pintype "passive"))
    )
    (net (code "86") (name "Net-(K30C-S)") (class "Default")
      (node (ref "K30") (pin "9") (pinfunction "S_9") (pintype "passive"))
      (node (ref "K32") (pin "13") (pinfunction "P_13") (pintype "passive"))
    )
    (net (code "87") (name "Net-(K32B-O)") (class "Default")
      (node (ref "JP3") (pin "10") (pinfunction "10_10") (pintype "passive"))
      (node (ref "K32") (pin "6") (pinfunction "O_6") (pintype "passive"))
    )
    (net (code "88") (name "unconnected-(JP4-Pad6)") (class "Default")
      (node (ref "JP4") (pin "6") (pinfunction "6_6") (pintype "passive"))
    )
    (net (code "89") (name "unconnected-(JP4-Pad7)") (class "Default")
      (node (ref "JP4") (pin "7") (pinfunction "7_7") (pintype "passive"))
    )
    (net (code "90") (name "unconnected-(JP4-Pad8)") (class "Default")
      (node (ref "JP4") (pin "8") (pinfunction "8_8") (pintype "passive"))
    )
    (net (code "91") (name "unconnected-(JP4-Pad9)") (class "Default")
      (node (ref "JP4") (pin "9") (pinfunction "9_9") (pintype "passive"))
    )
    (net (code "92") (name "unconnected-(JP4-Pad10)") (class "Default")
      (node (ref "JP4") (pin "10") (pinfunction "10_10") (pintype "passive"))
    )
    (net (code "93") (name "unconnected-(JP5-Pad6)") (class "Default")
      (node (ref "JP5") (pin "6") (pinfunction "6_6") (pintype "passive"))
    )
    (net (code "94") (name "unconnected-(JP5-Pad7)") (class "Default")
      (node (ref "JP5") (pin "7") (pinfunction "7_7") (pintype "passive"))
    )
    (net (code "95") (name "unconnected-(JP5-Pad8)") (class "Default")
      (node (ref "JP5") (pin "8") (pinfunction "8_8") (pintype "passive"))
    )
    (net (code "96") (name "unconnected-(JP5-Pad9)") (class "Default")
      (node (ref "JP5") (pin "9") (pinfunction "9_9") (pintype "passive"))
    )
    (net (code "97") (name "unconnected-(JP5-Pad10)") (class "Default")
      (node (ref "JP5") (pin "10") (pinfunction "10_10") (pintype "passive"))
    )
    (net (code "98") (name "unconnected-(JP6-Pad6)") (class "Default")
      (node (ref "JP6") (pin "6") (pinfunction "6_6") (pintype "passive"))
    )
    (net (code "99") (name "unconnected-(JP6-Pad7)") (class "Default")
      (node (ref "JP6") (pin "7") (pinfunction "7_7") (pintype "passive"))
    )
    (net (code "100") (name "unconnected-(JP6-Pad8)") (class "Default")
      (node (ref "JP6") (pin "8") (pinfunction "8_8") (pintype "passive"))
    )
    (net (code "101") (name "unconnected-(JP6-Pad9)") (class "Default")
      (node (ref "JP6") (pin "9") (pinfunction "9_9") (pintype "passive"))
    )
    (net (code "102") (name "unconnected-(JP6-Pad10)") (class "Default")
      (node (ref "JP6") (pin "10") (pinfunction "10_10") (pintype "passive"))
    )
    (net (code "103") (name "unconnected-(JP7-Pad6)") (class "Default")
      (node (ref "JP7") (pin "6") (pinfunction "6_6") (pintype "passive"))
    )
    (net (code "104") (name "unconnected-(JP7-Pad7)") (class "Default")
      (node (ref "JP7") (pin "7") (pinfunction "7_7") (pintype "passive"))
    )
    (net (code "105") (name "unconnected-(JP7-Pad8)") (class "Default")
      (node (ref "JP7") (pin "8") (pinfunction "8_8") (pintype "passive"))
    )
    (net (code "106") (name "unconnected-(JP7-Pad9)") (class "Default")
      (node (ref "JP7") (pin "9") (pinfunction "9_9") (pintype "passive"))
    )
    (net (code "107") (name "unconnected-(JP7-Pad10)") (class "Default")
      (node (ref "JP7") (pin "10") (pinfunction "10_10") (pintype "passive"))
    )
    (net (code "108") (name "unconnected-(JP8-Pad5)") (class "Default")
      (node (ref "JP8") (pin "5") (pinfunction "5_5") (pintype "passive"))
    )
    (net (code "109") (name "unconnected-(JP8-Pad6)") (class "Default")
      (node (ref "JP8") (pin "6") (pinfunction "6_6") (pintype "passive"))
    )
    (net (code "110") (name "unconnected-(JP8-Pad7)") (class "Default")
      (node (ref "JP8") (pin "7") (pinfunction "7_7") (pintype "passive"))
    )
    (net (code "111") (name "unconnected-(JP8-Pad8)") (class "Default")
      (node (ref "JP8") (pin "8") (pinfunction "8_8") (pintype "passive"))
    )
    (net (code "112") (name "unconnected-(JP8-Pad9)") (class "Default")
      (node (ref "JP8") (pin "9") (pinfunction "9_9") (pintype "passive"))
    )
    (net (code "113") (name "unconnected-(JP8-Pad10)") (class "Default")
      (node (ref "JP8") (pin "10") (pinfunction "10_10") (pintype "passive"))
    )
    (net (code "114") (name "unconnected-(JP9-Pad5)") (class "Default")
      (node (ref "JP9") (pin "5") (pinfunction "5_5") (pintype "passive"))
    )
    (net (code "115") (name "unconnected-(JP9-Pad6)") (class "Default")
      (node (ref "JP9") (pin "6") (pinfunction "6_6") (pintype "passive"))
    )
    (net (code "116") (name "unconnected-(JP9-Pad7)") (class "Default")
      (node (ref "JP9") (pin "7") (pinfunction "7_7") (pintype "passive"))
    )
    (net (code "117") (name "unconnected-(JP9-Pad8)") (class "Default")
      (node (ref "JP9") (pin "8") (pinfunction "8_8") (pintype "passive"))
    )
    (net (code "118") (name "unconnected-(JP9-Pad9)") (class "Default")
      (node (ref "JP9") (pin "9") (pinfunction "9_9") (pintype "passive"))
    )
    (net (code "119") (name "unconnected-(JP9-Pad10)") (class "Default")
      (node (ref "JP9") (pin "10") (pinfunction "10_10") (pintype "passive"))
    )
    (net (code "120") (name "unconnected-(JP10-Pad5)") (class "Default")
      (node (ref "JP10") (pin "5") (pinfunction "5_5") (pintype "passive"))
    )
    (net (code "121") (name "unconnected-(JP10-Pad6)") (class "Default")
      (node (ref "JP10") (pin "6") (pinfunction "6_6") (pintype "passive"))
    )
    (net (code "122") (name "unconnected-(JP10-Pad7)") (class "Default")
      (node (ref "JP10") (pin "7") (pinfunction "7_7") (pintype "passive"))
    )
    (net (code "123") (name "unconnected-(JP10-Pad8)") (class "Default")
      (node (ref "JP10") (pin "8") (pinfunction "8_8") (pintype "passive"))
    )
    (net (code "124") (name "unconnected-(JP10-Pad9)") (class "Default")
      (node (ref "JP10") (pin "9") (pinfunction "9_9") (pintype "passive"))
    )
    (net (code "125") (name "unconnected-(JP10-Pad10)") (class "Default")
      (node (ref "JP10") (pin "10") (pinfunction "10_10") (pintype "passive"))
    )
    (net (code "126") (name "unconnected-(K11B-S-Pad8)") (class "Default")
      (node (ref "K11") (pin "8") (pinfunction "S_8") (pintype "passive"))
    )
    (net (code "127") (name "unconnected-(K11C-O-Pad11)") (class "Default")
      (node (ref "K11") (pin "11") (pinfunction "O_11") (pintype "passive"))
    )
    (net (code "128") (name "unconnected-(K11C-S-Pad9)") (class "Default")
      (node (ref "K11") (pin "9") (pinfunction "S_9") (pintype "passive"))
    )
    (net (code "129") (name "unconnected-(K15B-O-Pad6)") (class "Default")
      (node (ref "K15") (pin "6") (pinfunction "O_6") (pintype "passive"))
    )
    (net (code "130") (name "unconnected-(K15B-S-Pad8)") (class "Default")
      (node (ref "K15") (pin "8") (pinfunction "S_8") (pintype "passive"))
    )
    (net (code "131") (name "unconnected-(K15C-O-Pad11)") (class "Default")
      (node (ref "K15") (pin "11") (pinfunction "O_11") (pintype "passive"))
    )
    (net (code "132") (name "unconnected-(K15C-S-Pad9)") (class "Default")
      (node (ref "K15") (pin "9") (pinfunction "S_9") (pintype "passive"))
    )
    (net (code "133") (name "unconnected-(K16B-S-Pad8)") (class "Default")
      (node (ref "K16") (pin "8") (pinfunction "S_8") (pintype "passive"))
    )
    (net (code "134") (name "unconnected-(K16C-O-Pad11)") (class "Default")
      (node (ref "K16") (pin "11") (pinfunction "O_11") (pintype "passive"))
    )
    (net (code "135") (name "unconnected-(K16C-S-Pad9)") (class "Default")
      (node (ref "K16") (pin "9") (pinfunction "S_9") (pintype "passive"))
    )
    (net (code "136") (name "unconnected-(K19B-O-Pad6)") (class "Default")
      (node (ref "K19") (pin "6") (pinfunction "O_6") (pintype "passive"))
    )
    (net (code "137") (name "unconnected-(K19B-S-Pad8)") (class "Default")
      (node (ref "K19") (pin "8") (pinfunction "S_8") (pintype "passive"))
    )
    (net (code "138") (name "unconnected-(K19C-O-Pad11)") (class "Default")
      (node (ref "K19") (pin "11") (pinfunction "O_11") (pintype "passive"))
    )
    (net (code "139") (name "unconnected-(K19C-S-Pad9)") (class "Default")
      (node (ref "K19") (pin "9") (pinfunction "S_9") (pintype "passive"))
    )
    (net (code "140") (name "unconnected-(K20B-S-Pad8)") (class "Default")
      (node (ref "K20") (pin "8") (pinfunction "S_8") (pintype "passive"))
    )
    (net (code "141") (name "unconnected-(K20C-O-Pad11)") (class "Default")
      (node (ref "K20") (pin "11") (pinfunction "O_11") (pintype "passive"))
    )
    (net (code "142") (name "unconnected-(K20C-S-Pad9)") (class "Default")
      (node (ref "K20") (pin "9") (pinfunction "S_9") (pintype "passive"))
    )
    (net (code "143") (name "unconnected-(K23B-O-Pad6)") (class "Default")
      (node (ref "K23") (pin "6") (pinfunction "O_6") (pintype "passive"))
    )
    (net (code "144") (name "unconnected-(K23B-S-Pad8)") (class "Default")
      (node (ref "K23") (pin "8") (pinfunction "S_8") (pintype "passive"))
    )
    (net (code "145") (name "unconnected-(K23C-O-Pad11)") (class "Default")
      (node (ref "K23") (pin "11") (pinfunction "O_11") (pintype "passive"))
    )
    (net (code "146") (name "unconnected-(K23C-S-Pad9)") (class "Default")
      (node (ref "K23") (pin "9") (pinfunction "S_9") (pintype "passive"))
    )
    (net (code "147") (name "unconnected-(K24B-S-Pad8)") (class "Default")
      (node (ref "K24") (pin "8") (pinfunction "S_8") (pintype "passive"))
    )
    (net (code "148") (name "unconnected-(K24C-O-Pad11)") (class "Default")
      (node (ref "K24") (pin "11") (pinfunction "O_11") (pintype "passive"))
    )
    (net (code "149") (name "unconnected-(K24C-S-Pad9)") (class "Default")
      (node (ref "K24") (pin "9") (pinfunction "S_9") (pintype "passive"))
    )
    (net (code "150") (name "unconnected-(K27B-O-Pad6)") (class "Default")
      (node (ref "K27") (pin "6") (pinfunction "O_6") (pintype "passive"))
    )
    (net (code "151") (name "unconnected-(K27B-S-Pad8)") (class "Default")
      (node (ref "K27") (pin "8") (pinfunction "S_8") (pintype "passive"))
    )
    (net (code "152") (name "unconnected-(K27C-O-Pad11)") (class "Default")
      (node (ref "K27") (pin "11") (pinfunction "O_11") (pintype "passive"))
    )
    (net (code "153") (name "unconnected-(K27C-S-Pad9)") (class "Default")
      (node (ref "K27") (pin "9") (pinfunction "S_9") (pintype "passive"))
    )
    (net (code "154") (name "unconnected-(K28B-S-Pad8)") (class "Default")
      (node (ref "K28") (pin "8") (pinfunction "S_8") (pintype "passive"))
    )
    (net (code "155") (name "unconnected-(K28C-O-Pad11)") (class "Default")
      (node (ref "K28") (pin "11") (pinfunction "O_11") (pintype "passive"))
    )
    (net (code "156") (name "unconnected-(K28C-S-Pad9)") (class "Default")
      (node (ref "K28") (pin "9") (pinfunction "S_9") (pintype "passive"))
    )
    (net (code "157") (name "unconnected-(K31B-O-Pad6)") (class "Default")
      (node (ref "K31") (pin "6") (pinfunction "O_6") (pintype "passive"))
    )
    (net (code "158") (name "unconnected-(K31B-S-Pad8)") (class "Default")
      (node (ref "K31") (pin "8") (pinfunction "S_8") (pintype "passive"))
    )
    (net (code "159") (name "unconnected-(K31C-O-Pad11)") (class "Default")
      (node (ref "K31") (pin "11") (pinfunction "O_11") (pintype "passive"))
    )
    (net (code "160") (name "unconnected-(K31C-S-Pad9)") (class "Default")
      (node (ref "K31") (pin "9") (pinfunction "S_9") (pintype "passive"))
    )
    (net (code "161") (name "unconnected-(K32B-S-Pad8)") (class "Default")
      (node (ref "K32") (pin "8") (pinfunction "S_8") (pintype "passive"))
    )
    (net (code "162") (name "unconnected-(K32C-O-Pad11)") (class "Default")
      (node (ref "K32") (pin "11") (pinfunction "O_11") (pintype "passive"))
    )
    (net (code "163") (name "unconnected-(K32C-S-Pad9)") (class "Default")
      (node (ref "K32") (pin "9") (pinfunction "S_9") (pintype "passive"))
    )
  )
)
